# etapa1_suma.net
KiCad netlist of a schematic drawn in Altium Designer
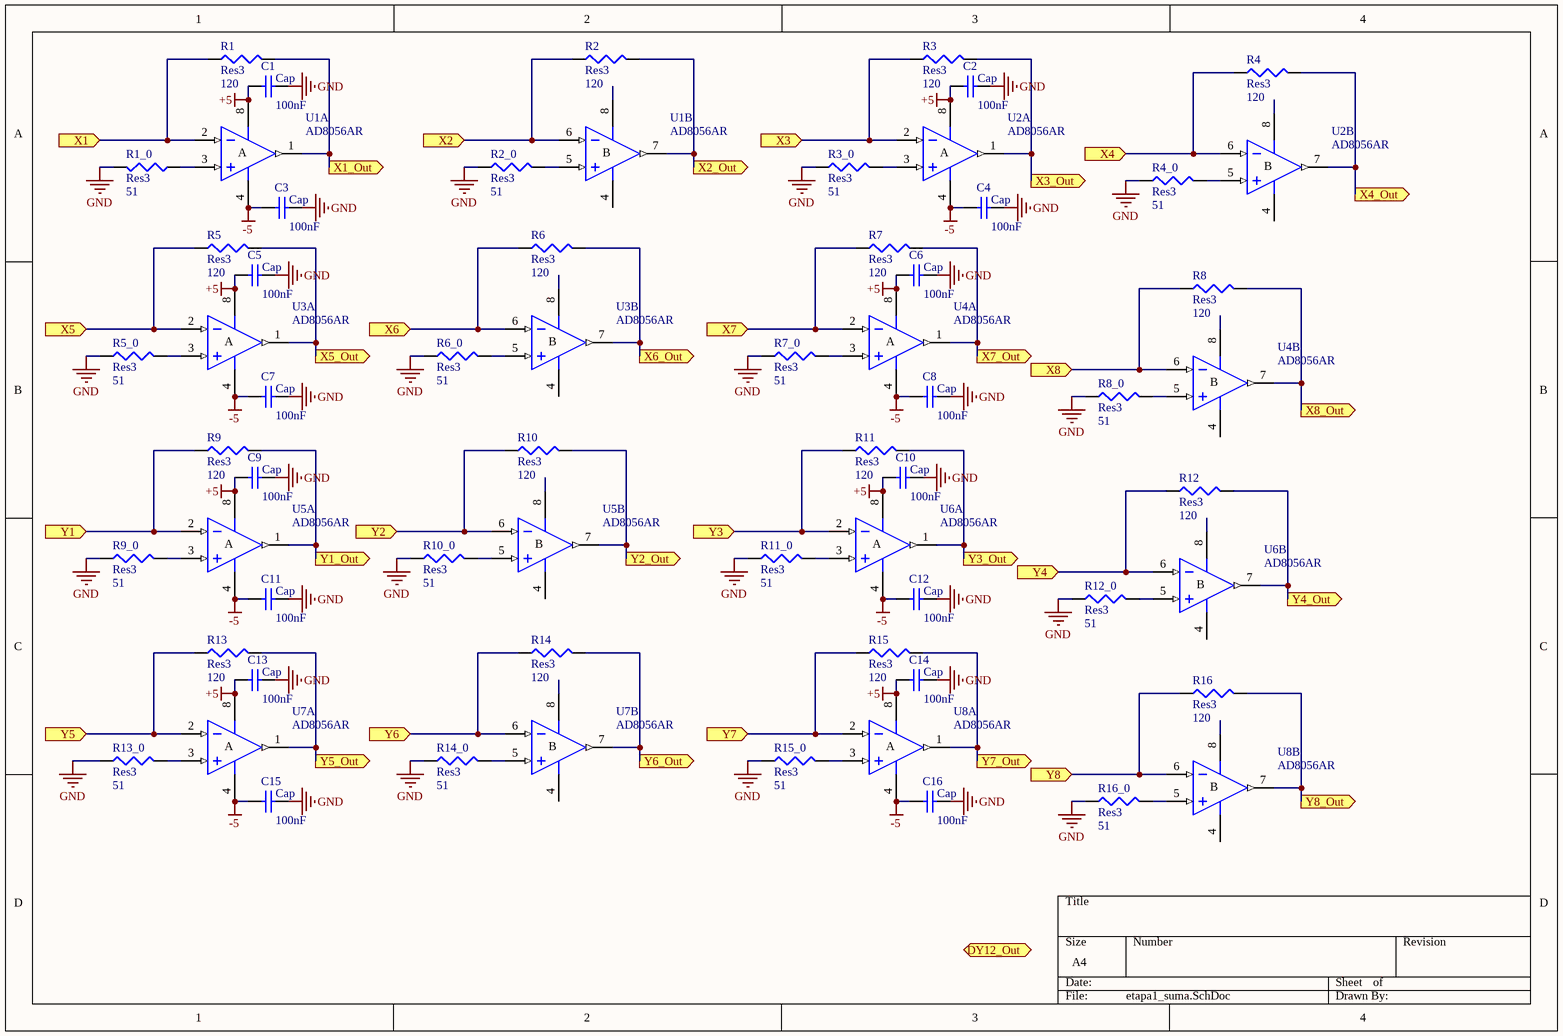
[diagram p0: etapa1_suma.SchDoc]

(export (version "E")
  (design (tool "Eeschema 10.0.6"))
  (components
    (comp (ref "C1")
      (value "Cap")
      (footprint "1608[0603]")
      (description "Capacitor")
      (fields (field (name "ALTIUM_VALUE") "100nF") (field (name "PUBLISHER") "Altium Limited"))
      (libsource (lib "Miscellaneous Devices") (part "Cap"))
    )
    (comp (ref "C2")
      (value "Cap")
      (footprint "1608[0603]")
      (description "Capacitor")
      (fields (field (name "ALTIUM_VALUE") "100nF") (field (name "PUBLISHER") "Altium Limited"))
      (libsource (lib "Miscellaneous Devices") (part "Cap"))
    )
    (comp (ref "C3")
      (value "Cap")
      (footprint "1608[0603]")
      (description "Capacitor")
      (fields (field (name "ALTIUM_VALUE") "100nF") (field (name "PUBLISHER") "Altium Limited"))
      (libsource (lib "Miscellaneous Devices") (part "Cap"))
    )
    (comp (ref "C4")
      (value "Cap")
      (footprint "1608[0603]")
      (description "Capacitor")
      (fields (field (name "ALTIUM_VALUE") "100nF") (field (name "PUBLISHER") "Altium Limited"))
      (libsource (lib "Miscellaneous Devices") (part "Cap"))
    )
    (comp (ref "C5")
      (value "Cap")
      (footprint "1608[0603]")
      (description "Capacitor")
      (fields (field (name "ALTIUM_VALUE") "100nF") (field (name "PUBLISHER") "Altium Limited"))
      (libsource (lib "Miscellaneous Devices") (part "Cap"))
    )
    (comp (ref "C6")
      (value "Cap")
      (footprint "1608[0603]")
      (description "Capacitor")
      (fields (field (name "ALTIUM_VALUE") "100nF") (field (name "PUBLISHER") "Altium Limited"))
      (libsource (lib "Miscellaneous Devices") (part "Cap"))
    )
    (comp (ref "C7")
      (value "Cap")
      (footprint "1608[0603]")
      (description "Capacitor")
      (fields (field (name "ALTIUM_VALUE") "100nF") (field (name "PUBLISHER") "Altium Limited"))
      (libsource (lib "Miscellaneous Devices") (part "Cap"))
    )
    (comp (ref "C8")
      (value "Cap")
      (footprint "1608[0603]")
      (description "Capacitor")
      (fields (field (name "ALTIUM_VALUE") "100nF") (field (name "PUBLISHER") "Altium Limited"))
      (libsource (lib "Miscellaneous Devices") (part "Cap"))
    )
    (comp (ref "C9")
      (value "Cap")
      (footprint "1608[0603]")
      (description "Capacitor")
      (fields (field (name "ALTIUM_VALUE") "100nF") (field (name "PUBLISHER") "Altium Limited"))
      (libsource (lib "Miscellaneous Devices") (part "Cap"))
    )
    (comp (ref "C10")
      (value "Cap")
      (footprint "1608[0603]")
      (description "Capacitor")
      (fields (field (name "ALTIUM_VALUE") "100nF") (field (name "PUBLISHER") "Altium Limited"))
      (libsource (lib "Miscellaneous Devices") (part "Cap"))
    )
    (comp (ref "C11")
      (value "Cap")
      (footprint "1608[0603]")
      (description "Capacitor")
      (fields (field (name "ALTIUM_VALUE") "100nF") (field (name "PUBLISHER") "Altium Limited"))
      (libsource (lib "Miscellaneous Devices") (part "Cap"))
    )
    (comp (ref "C12")
      (value "Cap")
      (footprint "1608[0603]")
      (description "Capacitor")
      (fields (field (name "ALTIUM_VALUE") "100nF") (field (name "PUBLISHER") "Altium Limited"))
      (libsource (lib "Miscellaneous Devices") (part "Cap"))
    )
    (comp (ref "C13")
      (value "Cap")
      (footprint "1608[0603]")
      (description "Capacitor")
      (fields (field (name "ALTIUM_VALUE") "100nF") (field (name "PUBLISHER") "Altium Limited"))
      (libsource (lib "Miscellaneous Devices") (part "Cap"))
    )
    (comp (ref "C14")
      (value "Cap")
      (footprint "1608[0603]")
      (description "Capacitor")
      (fields (field (name "ALTIUM_VALUE") "100nF") (field (name "PUBLISHER") "Altium Limited"))
      (libsource (lib "Miscellaneous Devices") (part "Cap"))
    )
    (comp (ref "C15")
      (value "Cap")
      (footprint "1608[0603]")
      (description "Capacitor")
      (fields (field (name "ALTIUM_VALUE") "100nF") (field (name "PUBLISHER") "Altium Limited"))
      (libsource (lib "Miscellaneous Devices") (part "Cap"))
    )
    (comp (ref "C16")
      (value "Cap")
      (footprint "1608[0603]")
      (description "Capacitor")
      (fields (field (name "ALTIUM_VALUE") "100nF") (field (name "PUBLISHER") "Altium Limited"))
      (libsource (lib "Miscellaneous Devices") (part "Cap"))
    )
    (comp (ref "R1")
      (value "Res3")
      (footprint "0402")
      (description "Resistor")
      (fields (field (name "ALTIUM_VALUE") "120") (field (name "PUBLISHER") "Altium Limited"))
      (libsource (lib "Miscellaneous Devices") (part "Res3"))
    )
    (comp (ref "R1_0")
      (value "Res3")
      (footprint "0402")
      (description "Resistor")
      (fields (field (name "ALTIUM_VALUE") "51") (field (name "PUBLISHER") "Altium Limited"))
      (libsource (lib "Miscellaneous Devices") (part "Res3"))
    )
    (comp (ref "R2")
      (value "Res3")
      (footprint "0402")
      (description "Resistor")
      (fields (field (name "ALTIUM_VALUE") "120") (field (name "PUBLISHER") "Altium Limited"))
      (libsource (lib "Miscellaneous Devices") (part "Res3"))
    )
    (comp (ref "R2_0")
      (value "Res3")
      (footprint "0402")
      (description "Resistor")
      (fields (field (name "ALTIUM_VALUE") "51") (field (name "PUBLISHER") "Altium Limited"))
      (libsource (lib "Miscellaneous Devices") (part "Res3"))
    )
    (comp (ref "R3")
      (value "Res3")
      (footprint "0402")
      (description "Resistor")
      (fields (field (name "ALTIUM_VALUE") "120") (field (name "PUBLISHER") "Altium Limited"))
      (libsource (lib "Miscellaneous Devices") (part "Res3"))
    )
    (comp (ref "R3_0")
      (value "Res3")
      (footprint "0402")
      (description "Resistor")
      (fields (field (name "ALTIUM_VALUE") "51") (field (name "PUBLISHER") "Altium Limited"))
      (libsource (lib "Miscellaneous Devices") (part "Res3"))
    )
    (comp (ref "R4")
      (value "Res3")
      (footprint "0402")
      (description "Resistor")
      (fields (field (name "ALTIUM_VALUE") "120") (field (name "PUBLISHER") "Altium Limited"))
      (libsource (lib "Miscellaneous Devices") (part "Res3"))
    )
    (comp (ref "R4_0")
      (value "Res3")
      (footprint "0402")
      (description "Resistor")
      (fields (field (name "ALTIUM_VALUE") "51") (field (name "PUBLISHER") "Altium Limited"))
      (libsource (lib "Miscellaneous Devices") (part "Res3"))
    )
    (comp (ref "R5")
      (value "Res3")
      (footprint "0402")
      (description "Resistor")
      (fields (field (name "ALTIUM_VALUE") "120") (field (name "PUBLISHER") "Altium Limited"))
      (libsource (lib "Miscellaneous Devices") (part "Res3"))
    )
    (comp (ref "R5_0")
      (value "Res3")
      (footprint "0402")
      (description "Resistor")
      (fields (field (name "ALTIUM_VALUE") "51") (field (name "PUBLISHER") "Altium Limited"))
      (libsource (lib "Miscellaneous Devices") (part "Res3"))
    )
    (comp (ref "R6")
      (value "Res3")
      (footprint "0402")
      (description "Resistor")
      (fields (field (name "ALTIUM_VALUE") "120") (field (name "PUBLISHER") "Altium Limited"))
      (libsource (lib "Miscellaneous Devices") (part "Res3"))
    )
    (comp (ref "R6_0")
      (value "Res3")
      (footprint "0402")
      (description "Resistor")
      (fields (field (name "ALTIUM_VALUE") "51") (field (name "PUBLISHER") "Altium Limited"))
      (libsource (lib "Miscellaneous Devices") (part "Res3"))
    )
    (comp (ref "R7")
      (value "Res3")
      (footprint "0402")
      (description "Resistor")
      (fields (field (name "ALTIUM_VALUE") "120") (field (name "PUBLISHER") "Altium Limited"))
      (libsource (lib "Miscellaneous Devices") (part "Res3"))
    )
    (comp (ref "R7_0")
      (value "Res3")
      (footprint "0402")
      (description "Resistor")
      (fields (field (name "ALTIUM_VALUE") "51") (field (name "PUBLISHER") "Altium Limited"))
      (libsource (lib "Miscellaneous Devices") (part "Res3"))
    )
    (comp (ref "R8")
      (value "Res3")
      (footprint "0402")
      (description "Resistor")
      (fields (field (name "ALTIUM_VALUE") "120") (field (name "PUBLISHER") "Altium Limited"))
      (libsource (lib "Miscellaneous Devices") (part "Res3"))
    )
    (comp (ref "R8_0")
      (value "Res3")
      (footprint "0402")
      (description "Resistor")
      (fields (field (name "ALTIUM_VALUE") "51") (field (name "PUBLISHER") "Altium Limited"))
      (libsource (lib "Miscellaneous Devices") (part "Res3"))
    )
    (comp (ref "R9")
      (value "Res3")
      (footprint "0402")
      (description "Resistor")
      (fields (field (name "ALTIUM_VALUE") "120") (field (name "PUBLISHER") "Altium Limited"))
      (libsource (lib "Miscellaneous Devices") (part "Res3"))
    )
    (comp (ref "R9_0")
      (value "Res3")
      (footprint "0402")
      (description "Resistor")
      (fields (field (name "ALTIUM_VALUE") "51") (field (name "PUBLISHER") "Altium Limited"))
      (libsource (lib "Miscellaneous Devices") (part "Res3"))
    )
    (comp (ref "R10")
      (value "Res3")
      (footprint "0402")
      (description "Resistor")
      (fields (field (name "ALTIUM_VALUE") "120") (field (name "PUBLISHER") "Altium Limited"))
      (libsource (lib "Miscellaneous Devices") (part "Res3"))
    )
    (comp (ref "R10_0")
      (value "Res3")
      (footprint "0402")
      (description "Resistor")
      (fields (field (name "ALTIUM_VALUE") "51") (field (name "PUBLISHER") "Altium Limited"))
      (libsource (lib "Miscellaneous Devices") (part "Res3"))
    )
    (comp (ref "R11")
      (value "Res3")
      (footprint "0402")
      (description "Resistor")
      (fields (field (name "ALTIUM_VALUE") "120") (field (name "PUBLISHER") "Altium Limited"))
      (libsource (lib "Miscellaneous Devices") (part "Res3"))
    )
    (comp (ref "R11_0")
      (value "Res3")
      (footprint "0402")
      (description "Resistor")
      (fields (field (name "ALTIUM_VALUE") "51") (field (name "PUBLISHER") "Altium Limited"))
      (libsource (lib "Miscellaneous Devices") (part "Res3"))
    )
    (comp (ref "R12")
      (value "Res3")
      (footprint "0402")
      (description "Resistor")
      (fields (field (name "ALTIUM_VALUE") "120") (field (name "PUBLISHER") "Altium Limited"))
      (libsource (lib "Miscellaneous Devices") (part "Res3"))
    )
    (comp (ref "R12_0")
      (value "Res3")
      (footprint "0402")
      (description "Resistor")
      (fields (field (name "ALTIUM_VALUE") "51") (field (name "PUBLISHER") "Altium Limited"))
      (libsource (lib "Miscellaneous Devices") (part "Res3"))
    )
    (comp (ref "R13")
      (value "Res3")
      (footprint "0402")
      (description "Resistor")
      (fields (field (name "ALTIUM_VALUE") "120") (field (name "PUBLISHER") "Altium Limited"))
      (libsource (lib "Miscellaneous Devices") (part "Res3"))
    )
    (comp (ref "R13_0")
      (value "Res3")
      (footprint "0402")
      (description "Resistor")
      (fields (field (name "ALTIUM_VALUE") "51") (field (name "PUBLISHER") "Altium Limited"))
      (libsource (lib "Miscellaneous Devices") (part "Res3"))
    )
    (comp (ref "R14")
      (value "Res3")
      (footprint "0402")
      (description "Resistor")
      (fields (field (name "ALTIUM_VALUE") "120") (field (name "PUBLISHER") "Altium Limited"))
      (libsource (lib "Miscellaneous Devices") (part "Res3"))
    )
    (comp (ref "R14_0")
      (value "Res3")
      (footprint "0402")
      (description "Resistor")
      (fields (field (name "ALTIUM_VALUE") "51") (field (name "PUBLISHER") "Altium Limited"))
      (libsource (lib "Miscellaneous Devices") (part "Res3"))
    )
    (comp (ref "R15")
      (value "Res3")
      (footprint "0402")
      (description "Resistor")
      (fields (field (name "ALTIUM_VALUE") "120") (field (name "PUBLISHER") "Altium Limited"))
      (libsource (lib "Miscellaneous Devices") (part "Res3"))
    )
    (comp (ref "R15_0")
      (value "Res3")
      (footprint "0402")
      (description "Resistor")
      (fields (field (name "ALTIUM_VALUE") "51") (field (name "PUBLISHER") "Altium Limited"))
      (libsource (lib "Miscellaneous Devices") (part "Res3"))
    )
    (comp (ref "R16")
      (value "Res3")
      (footprint "0402")
      (description "Resistor")
      (fields (field (name "ALTIUM_VALUE") "120") (field (name "PUBLISHER") "Altium Limited"))
      (libsource (lib "Miscellaneous Devices") (part "Res3"))
    )
    (comp (ref "R16_0")
      (value "Res3")
      (footprint "0402")
      (description "Resistor")
      (fields (field (name "ALTIUM_VALUE") "51") (field (name "PUBLISHER") "Altium Limited"))
      (libsource (lib "Miscellaneous Devices") (part "Res3"))
    )
    (comp (ref "U1")
      (value "AD8056AR")
      (footprint "RM-8")
      (description "Low Cost, 300MHz Voltage Feedback Amplifier")
      (fields (field (name "PUBLISHER") "Altium Limited"))
      (libsource (lib "AD Operational Amplifier") (part "AD8056AR"))
    )
    (comp (ref "U2")
      (value "AD8056AR")
      (footprint "RM-8")
      (description "Low Cost, 300MHz Voltage Feedback Amplifier")
      (fields (field (name "PUBLISHER") "Altium Limited"))
      (libsource (lib "AD Operational Amplifier") (part "AD8056AR"))
    )
    (comp (ref "U3")
      (value "AD8056AR")
      (footprint "RM-8")
      (description "Low Cost, 300MHz Voltage Feedback Amplifier")
      (fields (field (name "PUBLISHER") "Altium Limited"))
      (libsource (lib "AD Operational Amplifier") (part "AD8056AR"))
    )
    (comp (ref "U4")
      (value "AD8056AR")
      (footprint "RM-8")
      (description "Low Cost, 300MHz Voltage Feedback Amplifier")
      (fields (field (name "PUBLISHER") "Altium Limited"))
      (libsource (lib "AD Operational Amplifier") (part "AD8056AR"))
    )
    (comp (ref "U5")
      (value "AD8056AR")
      (footprint "RM-8")
      (description "Low Cost, 300MHz Voltage Feedback Amplifier")
      (fields (field (name "PUBLISHER") "Altium Limited"))
      (libsource (lib "AD Operational Amplifier") (part "AD8056AR"))
    )
    (comp (ref "U6")
      (value "AD8056AR")
      (footprint "RM-8")
      (description "Low Cost, 300MHz Voltage Feedback Amplifier")
      (fields (field (name "PUBLISHER") "Altium Limited"))
      (libsource (lib "AD Operational Amplifier") (part "AD8056AR"))
    )
    (comp (ref "U7")
      (value "AD8056AR")
      (footprint "RM-8")
      (description "Low Cost, 300MHz Voltage Feedback Amplifier")
      (fields (field (name "PUBLISHER") "Altium Limited"))
      (libsource (lib "AD Operational Amplifier") (part "AD8056AR"))
    )
    (comp (ref "U8")
      (value "AD8056AR")
      (footprint "RM-8")
      (description "Low Cost, 300MHz Voltage Feedback Amplifier")
      (fields (field (name "PUBLISHER") "Altium Limited"))
      (libsource (lib "AD Operational Amplifier") (part "AD8056AR"))
    )
  )
  (nets
    (net (code "1") (name "+5") (class "Default")
      (node (ref "C1") (pin "2") (pinfunction "2_2") (pintype "passive"))
      (node (ref "C10") (pin "2") (pinfunction "2_2") (pintype "passive"))
      (node (ref "C13") (pin "2") (pinfunction "2_2") (pintype "passive"))
      (node (ref "C14") (pin "2") (pinfunction "2_2") (pintype "passive"))
      (node (ref "C2") (pin "2") (pinfunction "2_2") (pintype "passive"))
      (node (ref "C5") (pin "2") (pinfunction "2_2") (pintype "passive"))
      (node (ref "C6") (pin "2") (pinfunction "2_2") (pintype "passive"))
      (node (ref "C9") (pin "2") (pinfunction "2_2") (pintype "passive"))
      (node (ref "U1") (pin "8") (pinfunction "V+_8") (pintype "power_in"))
      (node (ref "U2") (pin "8") (pinfunction "V+_8") (pintype "power_in"))
      (node (ref "U3") (pin "8") (pinfunction "V+_8") (pintype "power_in"))
      (node (ref "U4") (pin "8") (pinfunction "V+_8") (pintype "power_in"))
      (node (ref "U5") (pin "8") (pinfunction "V+_8") (pintype "power_in"))
      (node (ref "U6") (pin "8") (pinfunction "V+_8") (pintype "power_in"))
      (node (ref "U7") (pin "8") (pinfunction "V+_8") (pintype "power_in"))
      (node (ref "U8") (pin "8") (pinfunction "V+_8") (pintype "power_in"))
    )
    (net (code "2") (name "-5") (class "Default")
      (node (ref "C11") (pin "2") (pinfunction "2_2") (pintype "passive"))
      (node (ref "C12") (pin "2") (pinfunction "2_2") (pintype "passive"))
      (node (ref "C15") (pin "2") (pinfunction "2_2") (pintype "passive"))
      (node (ref "C16") (pin "2") (pinfunction "2_2") (pintype "passive"))
      (node (ref "C3") (pin "2") (pinfunction "2_2") (pintype "passive"))
      (node (ref "C4") (pin "2") (pinfunction "2_2") (pintype "passive"))
      (node (ref "C7") (pin "2") (pinfunction "2_2") (pintype "passive"))
      (node (ref "C8") (pin "2") (pinfunction "2_2") (pintype "passive"))
      (node (ref "U1") (pin "4") (pinfunction "V-_4") (pintype "power_in"))
      (node (ref "U2") (pin "4") (pinfunction "V-_4") (pintype "power_in"))
      (node (ref "U3") (pin "4") (pinfunction "V-_4") (pintype "power_in"))
      (node (ref "U4") (pin "4") (pinfunction "V-_4") (pintype "power_in"))
      (node (ref "U5") (pin "4") (pinfunction "V-_4") (pintype "power_in"))
      (node (ref "U6") (pin "4") (pinfunction "V-_4") (pintype "power_in"))
      (node (ref "U7") (pin "4") (pinfunction "V-_4") (pintype "power_in"))
      (node (ref "U8") (pin "4") (pinfunction "V-_4") (pintype "power_in"))
    )
    (net (code "4") (name "/X1") (class "Default")
      (node (ref "R1") (pin "1") (pinfunction "1_1") (pintype "passive"))
      (node (ref "U1") (pin "2") (pinfunction "IN-_2") (pintype "input"))
    )
    (net (code "5") (name "/X1_Out") (class "Default")
      (node (ref "R1") (pin "2") (pinfunction "2_2") (pintype "passive"))
      (node (ref "U1") (pin "1") (pinfunction "OUT_1") (pintype "output"))
    )
    (net (code "6") (name "/X2") (class "Default")
      (node (ref "R2") (pin "1") (pinfunction "1_1") (pintype "passive"))
      (node (ref "U1") (pin "6") (pinfunction "IN-_6") (pintype "input"))
    )
    (net (code "7") (name "/X2_Out") (class "Default")
      (node (ref "R2") (pin "2") (pinfunction "2_2") (pintype "passive"))
      (node (ref "U1") (pin "7") (pinfunction "OUT_7") (pintype "output"))
    )
    (net (code "8") (name "/X3") (class "Default")
      (node (ref "R3") (pin "1") (pinfunction "1_1") (pintype "passive"))
      (node (ref "U2") (pin "2") (pinfunction "IN-_2") (pintype "input"))
    )
    (net (code "9") (name "/X3_Out") (class "Default")
      (node (ref "R3") (pin "2") (pinfunction "2_2") (pintype "passive"))
      (node (ref "U2") (pin "1") (pinfunction "OUT_1") (pintype "output"))
    )
    (net (code "10") (name "/X4") (class "Default")
      (node (ref "R4") (pin "1") (pinfunction "1_1") (pintype "passive"))
      (node (ref "U2") (pin "6") (pinfunction "IN-_6") (pintype "input"))
    )
    (net (code "11") (name "/X4_Out") (class "Default")
      (node (ref "R4") (pin "2") (pinfunction "2_2") (pintype "passive"))
      (node (ref "U2") (pin "7") (pinfunction "OUT_7") (pintype "output"))
    )
    (net (code "12") (name "/X5") (class "Default")
      (node (ref "R5") (pin "1") (pinfunction "1_1") (pintype "passive"))
      (node (ref "U3") (pin "2") (pinfunction "IN-_2") (pintype "input"))
    )
    (net (code "13") (name "/X5_Out") (class "Default")
      (node (ref "R5") (pin "2") (pinfunction "2_2") (pintype "passive"))
      (node (ref "U3") (pin "1") (pinfunction "OUT_1") (pintype "output"))
    )
    (net (code "14") (name "/X6") (class "Default")
      (node (ref "R6") (pin "1") (pinfunction "1_1") (pintype "passive"))
      (node (ref "U3") (pin "6") (pinfunction "IN-_6") (pintype "input"))
    )
    (net (code "15") (name "/X6_Out") (class "Default")
      (node (ref "R6") (pin "2") (pinfunction "2_2") (pintype "passive"))
      (node (ref "U3") (pin "7") (pinfunction "OUT_7") (pintype "output"))
    )
    (net (code "16") (name "/X7") (class "Default")
      (node (ref "R7") (pin "1") (pinfunction "1_1") (pintype "passive"))
      (node (ref "U4") (pin "2") (pinfunction "IN-_2") (pintype "input"))
    )
    (net (code "17") (name "/X7_Out") (class "Default")
      (node (ref "R7") (pin "2") (pinfunction "2_2") (pintype "passive"))
      (node (ref "U4") (pin "1") (pinfunction "OUT_1") (pintype "output"))
    )
    (net (code "18") (name "/X8") (class "Default")
      (node (ref "R8") (pin "1") (pinfunction "1_1") (pintype "passive"))
      (node (ref "U4") (pin "6") (pinfunction "IN-_6") (pintype "input"))
    )
    (net (code "19") (name "/X8_Out") (class "Default")
      (node (ref "R8") (pin "2") (pinfunction "2_2") (pintype "passive"))
      (node (ref "U4") (pin "7") (pinfunction "OUT_7") (pintype "output"))
    )
    (net (code "20") (name "/Y1") (class "Default")
      (node (ref "R9") (pin "1") (pinfunction "1_1") (pintype "passive"))
      (node (ref "U5") (pin "2") (pinfunction "IN-_2") (pintype "input"))
    )
    (net (code "21") (name "/Y1_Out") (class "Default")
      (node (ref "R9") (pin "2") (pinfunction "2_2") (pintype "passive"))
      (node (ref "U5") (pin "1") (pinfunction "OUT_1") (pintype "output"))
    )
    (net (code "22") (name "/Y2") (class "Default")
      (node (ref "R10") (pin "1") (pinfunction "1_1") (pintype "passive"))
      (node (ref "U5") (pin "6") (pinfunction "IN-_6") (pintype "input"))
    )
    (net (code "23") (name "/Y2_Out") (class "Default")
      (node (ref "R10") (pin "2") (pinfunction "2_2") (pintype "passive"))
      (node (ref "U5") (pin "7") (pinfunction "OUT_7") (pintype "output"))
    )
    (net (code "24") (name "/Y3") (class "Default")
      (node (ref "R11") (pin "1") (pinfunction "1_1") (pintype "passive"))
      (node (ref "U6") (pin "2") (pinfunction "IN-_2") (pintype "input"))
    )
    (net (code "25") (name "/Y3_Out") (class "Default")
      (node (ref "R11") (pin "2") (pinfunction "2_2") (pintype "passive"))
      (node (ref "U6") (pin "1") (pinfunction "OUT_1") (pintype "output"))
    )
    (net (code "26") (name "/Y4") (class "Default")
      (node (ref "R12") (pin "1") (pinfunction "1_1") (pintype "passive"))
      (node (ref "U6") (pin "6") (pinfunction "IN-_6") (pintype "input"))
    )
    (net (code "27") (name "/Y4_Out") (class "Default")
      (node (ref "R12") (pin "2") (pinfunction "2_2") (pintype "passive"))
      (node (ref "U6") (pin "7") (pinfunction "OUT_7") (pintype "output"))
    )
    (net (code "28") (name "/Y5") (class "Default")
      (node (ref "R13") (pin "1") (pinfunction "1_1") (pintype "passive"))
      (node (ref "U7") (pin "2") (pinfunction "IN-_2") (pintype "input"))
    )
    (net (code "29") (name "/Y5_Out") (class "Default")
      (node (ref "R13") (pin "2") (pinfunction "2_2") (pintype "passive"))
      (node (ref "U7") (pin "1") (pinfunction "OUT_1") (pintype "output"))
    )
    (net (code "30") (name "/Y6") (class "Default")
      (node (ref "R14") (pin "1") (pinfunction "1_1") (pintype "passive"))
      (node (ref "U7") (pin "6") (pinfunction "IN-_6") (pintype "input"))
    )
    (net (code "31") (name "/Y6_Out") (class "Default")
      (node (ref "R14") (pin "2") (pinfunction "2_2") (pintype "passive"))
      (node (ref "U7") (pin "7") (pinfunction "OUT_7") (pintype "output"))
    )
    (net (code "32") (name "/Y7") (class "Default")
      (node (ref "R15") (pin "1") (pinfunction "1_1") (pintype "passive"))
      (node (ref "U8") (pin "2") (pinfunction "IN-_2") (pintype "input"))
    )
    (net (code "33") (name "/Y7_Out") (class "Default")
      (node (ref "R15") (pin "2") (pinfunction "2_2") (pintype "passive"))
      (node (ref "U8") (pin "1") (pinfunction "OUT_1") (pintype "output"))
    )
    (net (code "34") (name "/Y8") (class "Default")
      (node (ref "R16") (pin "1") (pinfunction "1_1") (pintype "passive"))
      (node (ref "U8") (pin "6") (pinfunction "IN-_6") (pintype "input"))
    )
    (net (code "35") (name "/Y8_Out") (class "Default")
      (node (ref "R16") (pin "2") (pinfunction "2_2") (pintype "passive"))
      (node (ref "U8") (pin "7") (pinfunction "OUT_7") (pintype "output"))
    )
    (net (code "36") (name "GND") (class "Default")
      (node (ref "C1") (pin "1") (pinfunction "1_1") (pintype "passive"))
      (node (ref "C10") (pin "1") (pinfunction "1_1") (pintype "passive"))
      (node (ref "C11") (pin "1") (pinfunction "1_1") (pintype "passive"))
      (node (ref "C12") (pin "1") (pinfunction "1_1") (pintype "passive"))
      (node (ref "C13") (pin "1") (pinfunction "1_1") (pintype "passive"))
      (node (ref "C14") (pin "1") (pinfunction "1_1") (pintype "passive"))
      (node (ref "C15") (pin "1") (pinfunction "1_1") (pintype "passive"))
      (node (ref "C16") (pin "1") (pinfunction "1_1") (pintype "passive"))
      (node (ref "C2") (pin "1") (pinfunction "1_1") (pintype "passive"))
      (node (ref "C3") (pin "1") (pinfunction "1_1") (pintype "passive"))
      (node (ref "C4") (pin "1") (pinfunction "1_1") (pintype "passive"))
      (node (ref "C5") (pin "1") (pinfunction "1_1") (pintype "passive"))
      (node (ref "C6") (pin "1") (pinfunction "1_1") (pintype "passive"))
      (node (ref "C7") (pin "1") (pinfunction "1_1") (pintype "passive"))
      (node (ref "C8") (pin "1") (pinfunction "1_1") (pintype "passive"))
      (node (ref "C9") (pin "1") (pinfunction "1_1") (pintype "passive"))
      (node (ref "R10_0") (pin "1") (pinfunction "1_1") (pintype "passive"))
      (node (ref "R11_0") (pin "1") (pinfunction "1_1") (pintype "passive"))
      (node (ref "R12_0") (pin "1") (pinfunction "1_1") (pintype "passive"))
      (node (ref "R13_0") (pin "1") (pinfunction "1_1") (pintype "passive"))
      (node (ref "R14_0") (pin "1") (pinfunction "1_1") (pintype "passive"))
      (node (ref "R15_0") (pin "1") (pinfunction "1_1") (pintype "passive"))
      (node (ref "R16_0") (pin "1") (pinfunction "1_1") (pintype "passive"))
      (node (ref "R1_0") (pin "2") (pinfunction "2_2") (pintype "passive"))
      (node (ref "R2_0") (pin "1") (pinfunction "1_1") (pintype "passive"))
      (node (ref "R3_0") (pin "1") (pinfunction "1_1") (pintype "passive"))
      (node (ref "R4_0") (pin "1") (pinfunction "1_1") (pintype "passive"))
      (node (ref "R5_0") (pin "1") (pinfunction "1_1") (pintype "passive"))
      (node (ref "R6_0") (pin "1") (pinfunction "1_1") (pintype "passive"))
      (node (ref "R7_0") (pin "1") (pinfunction "1_1") (pintype "passive"))
      (node (ref "R8_0") (pin "1") (pinfunction "1_1") (pintype "passive"))
      (node (ref "R9_0") (pin "1") (pinfunction "1_1") (pintype "passive"))
    )
    (net (code "37") (name "Net-(U1A-IN+)") (class "Default")
      (node (ref "R1_0") (pin "1") (pinfunction "1_1") (pintype "passive"))
      (node (ref "U1") (pin "3") (pinfunction "IN+_3") (pintype "input"))
    )
    (net (code "38") (name "Net-(U1B-IN+)") (class "Default")
      (node (ref "R2_0") (pin "2") (pinfunction "2_2") (pintype "passive"))
      (node (ref "U1") (pin "5") (pinfunction "IN+_5") (pintype "input"))
    )
    (net (code "39") (name "Net-(U2A-IN+)") (class "Default")
      (node (ref "R3_0") (pin "2") (pinfunction "2_2") (pintype "passive"))
      (node (ref "U2") (pin "3") (pinfunction "IN+_3") (pintype "input"))
    )
    (net (code "40") (name "Net-(U2B-IN+)") (class "Default")
      (node (ref "R4_0") (pin "2") (pinfunction "2_2") (pintype "passive"))
      (node (ref "U2") (pin "5") (pinfunction "IN+_5") (pintype "input"))
    )
    (net (code "41") (name "Net-(U3A-IN+)") (class "Default")
      (node (ref "R5_0") (pin "2") (pinfunction "2_2") (pintype "passive"))
      (node (ref "U3") (pin "3") (pinfunction "IN+_3") (pintype "input"))
    )
    (net (code "42") (name "Net-(U3B-IN+)") (class "Default")
      (node (ref "R6_0") (pin "2") (pinfunction "2_2") (pintype "passive"))
      (node (ref "U3") (pin "5") (pinfunction "IN+_5") (pintype "input"))
    )
    (net (code "43") (name "Net-(U4A-IN+)") (class "Default")
      (node (ref "R7_0") (pin "2") (pinfunction "2_2") (pintype "passive"))
      (node (ref "U4") (pin "3") (pinfunction "IN+_3") (pintype "input"))
    )
    (net (code "44") (name "Net-(U4B-IN+)") (class "Default")
      (node (ref "R8_0") (pin "2") (pinfunction "2_2") (pintype "passive"))
      (node (ref "U4") (pin "5") (pinfunction "IN+_5") (pintype "input"))
    )
    (net (code "45") (name "Net-(U5A-IN+)") (class "Default")
      (node (ref "R9_0") (pin "2") (pinfunction "2_2") (pintype "passive"))
      (node (ref "U5") (pin "3") (pinfunction "IN+_3") (pintype "input"))
    )
    (net (code "46") (name "Net-(U5B-IN+)") (class "Default")
      (node (ref "R10_0") (pin "2") (pinfunction "2_2") (pintype "passive"))
      (node (ref "U5") (pin "5") (pinfunction "IN+_5") (pintype "input"))
    )
    (net (code "47") (name "Net-(U6A-IN+)") (class "Default")
      (node (ref "R11_0") (pin "2") (pinfunction "2_2") (pintype "passive"))
      (node (ref "U6") (pin "3") (pinfunction "IN+_3") (pintype "input"))
    )
    (net (code "48") (name "Net-(U6B-IN+)") (class "Default")
      (node (ref "R12_0") (pin "2") (pinfunction "2_2") (pintype "passive"))
      (node (ref "U6") (pin "5") (pinfunction "IN+_5") (pintype "input"))
    )
    (net (code "49") (name "Net-(U7A-IN+)") (class "Default")
      (node (ref "R13_0") (pin "2") (pinfunction "2_2") (pintype "passive"))
      (node (ref "U7") (pin "3") (pinfunction "IN+_3") (pintype "input"))
    )
    (net (code "50") (name "Net-(U7B-IN+)") (class "Default")
      (node (ref "R14_0") (pin "2") (pinfunction "2_2") (pintype "passive"))
      (node (ref "U7") (pin "5") (pinfunction "IN+_5") (pintype "input"))
    )
    (net (code "51") (name "Net-(U8A-IN+)") (class "Default")
      (node (ref "R15_0") (pin "2") (pinfunction "2_2") (pintype "passive"))
      (node (ref "U8") (pin "3") (pinfunction "IN+_3") (pintype "input"))
    )
    (net (code "52") (name "Net-(U8B-IN+)") (class "Default")
      (node (ref "R16_0") (pin "2") (pinfunction "2_2") (pintype "passive"))
      (node (ref "U8") (pin "5") (pinfunction "IN+_5") (pintype "input"))
    )
    (net (code "53") (name "unconnected-(U1B-V+-Pad8)") (class "Default")
      (node (ref "U1") (pin "8") (pinfunction "V+_8") (pintype "power_in"))
    )
    (net (code "54") (name "unconnected-(U1B-V--Pad4)") (class "Default")
      (node (ref "U1") (pin "4") (pinfunction "V-_4") (pintype "power_in"))
    )
    (net (code "55") (name "unconnected-(U2B-V+-Pad8)") (class "Default")
      (node (ref "U2") (pin "8") (pinfunction "V+_8") (pintype "power_in"))
    )
    (net (code "56") (name "unconnected-(U2B-V--Pad4)") (class "Default")
      (node (ref "U2") (pin "4") (pinfunction "V-_4") (pintype "power_in"))
    )
    (net (code "57") (name "unconnected-(U3B-V+-Pad8)") (class "Default")
      (node (ref "U3") (pin "8") (pinfunction "V+_8") (pintype "power_in"))
    )
    (net (code "58") (name "unconnected-(U3B-V--Pad4)") (class "Default")
      (node (ref "U3") (pin "4") (pinfunction "V-_4") (pintype "power_in"))
    )
    (net (code "59") (name "unconnected-(U4B-V+-Pad8)") (class "Default")
      (node (ref "U4") (pin "8") (pinfunction "V+_8") (pintype "power_in"))
    )
    (net (code "60") (name "unconnected-(U4B-V--Pad4)") (class "Default")
      (node (ref "U4") (pin "4") (pinfunction "V-_4") (pintype "power_in"))
    )
    (net (code "61") (name "unconnected-(U5B-V+-Pad8)") (class "Default")
      (node (ref "U5") (pin "8") (pinfunction "V+_8") (pintype "power_in"))
    )
    (net (code "62") (name "unconnected-(U5B-V--Pad4)") (class "Default")
      (node (ref "U5") (pin "4") (pinfunction "V-_4") (pintype "power_in"))
    )
    (net (code "63") (name "unconnected-(U6B-V+-Pad8)") (class "Default")
      (node (ref "U6") (pin "8") (pinfunction "V+_8") (pintype "power_in"))
    )
    (net (code "64") (name "unconnected-(U6B-V--Pad4)") (class "Default")
      (node (ref "U6") (pin "4") (pinfunction "V-_4") (pintype "power_in"))
    )
    (net (code "65") (name "unconnected-(U7B-V+-Pad8)") (class "Default")
      (node (ref "U7") (pin "8") (pinfunction "V+_8") (pintype "power_in"))
    )
    (net (code "66") (name "unconnected-(U7B-V--Pad4)") (class "Default")
      (node (ref "U7") (pin "4") (pinfunction "V-_4") (pintype "power_in"))
    )
    (net (code "67") (name "unconnected-(U8B-V+-Pad8)") (class "Default")
      (node (ref "U8") (pin "8") (pinfunction "V+_8") (pintype "power_in"))
    )
    (net (code "68") (name "unconnected-(U8B-V--Pad4)") (class "Default")
      (node (ref "U8") (pin "4") (pinfunction "V-_4") (pintype "power_in"))
    )
  )
)
